# 03-Ethernet.net
KiCad netlist of a schematic drawn in Altium Designer
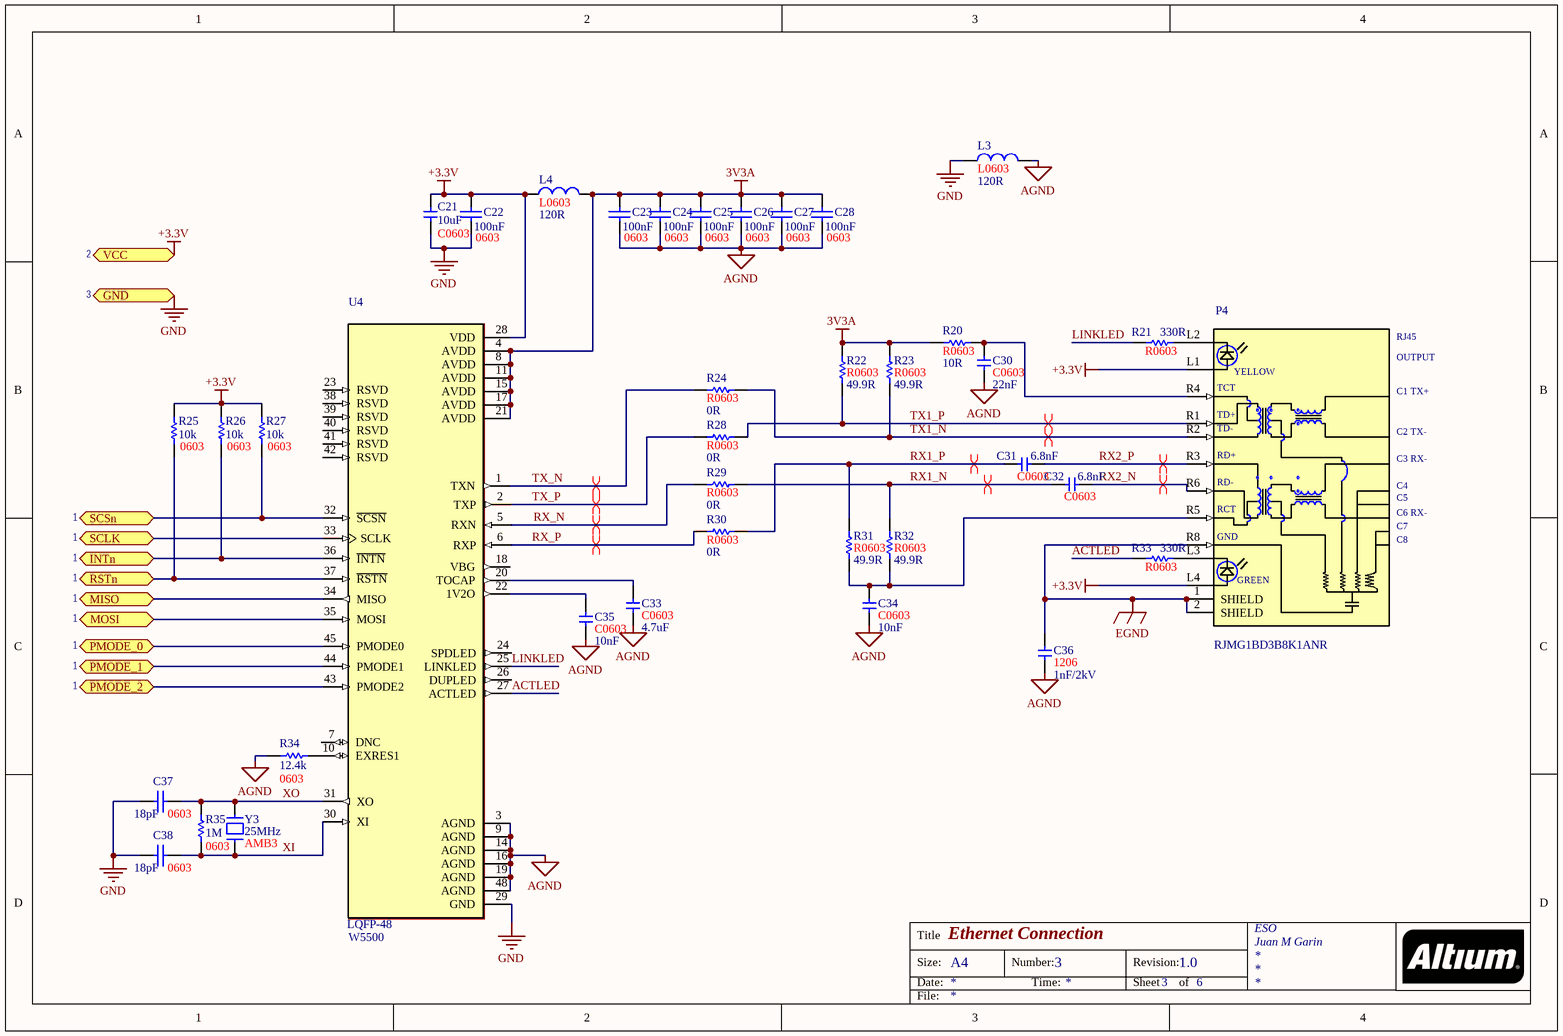
[diagram p0: 03-Ethernet.SchDoc]

(export (version "E")
  (design (tool "Eeschema 10.0.6"))
  (components
    (comp (ref "C21")
      (value "10uF")
      (footprint "C0603")
      (description "Capacitor")
      (fields
        (field (name "MANUFACTURER PART NUMBER") "JMK107ABJ106MA-T")
        (field (name "PACKAGEREFERENCE") "C0603")
      )
      (libsource (lib "schematic_library") (part "Cap_0603"))
    )
    (comp (ref "C22")
      (value "100nF")
      (footprint "C0603")
      (description "Capacitor (Semiconductor SIM Model)")
      (fields
        (field (name "MANUFACTURER PART NUMBER") "CL10F104ZO8NNNC")
        (field (name "PACKAGEREFERENCE") "0603")
      )
      (libsource (lib "Miscellaneous Devices") (part "Cap Semi"))
    )
    (comp (ref "C23")
      (value "100nF")
      (footprint "C0603")
      (description "Capacitor (Semiconductor SIM Model)")
      (fields
        (field (name "MANUFACTURER PART NUMBER") "CL10F104ZO8NNNC")
        (field (name "PACKAGEREFERENCE") "0603")
      )
      (libsource (lib "Miscellaneous Devices") (part "Cap Semi"))
    )
    (comp (ref "C24")
      (value "100nF")
      (footprint "C0603")
      (description "Capacitor (Semiconductor SIM Model)")
      (fields
        (field (name "MANUFACTURER PART NUMBER") "CL10F104ZO8NNNC")
        (field (name "PACKAGEREFERENCE") "0603")
      )
      (libsource (lib "Miscellaneous Devices") (part "Cap Semi"))
    )
    (comp (ref "C25")
      (value "100nF")
      (footprint "C0603")
      (description "Capacitor (Semiconductor SIM Model)")
      (fields
        (field (name "MANUFACTURER PART NUMBER") "CL10F104ZO8NNNC")
        (field (name "PACKAGEREFERENCE") "0603")
      )
      (libsource (lib "Miscellaneous Devices") (part "Cap Semi"))
    )
    (comp (ref "C26")
      (value "100nF")
      (footprint "C0603")
      (description "Capacitor (Semiconductor SIM Model)")
      (fields
        (field (name "MANUFACTURER PART NUMBER") "CL10F104ZO8NNNC")
        (field (name "PACKAGEREFERENCE") "0603")
      )
      (libsource (lib "Miscellaneous Devices") (part "Cap Semi"))
    )
    (comp (ref "C27")
      (value "100nF")
      (footprint "C0603")
      (description "Capacitor (Semiconductor SIM Model)")
      (fields
        (field (name "MANUFACTURER PART NUMBER") "CL10F104ZO8NNNC")
        (field (name "PACKAGEREFERENCE") "0603")
      )
      (libsource (lib "Miscellaneous Devices") (part "Cap Semi"))
    )
    (comp (ref "C28")
      (value "100nF")
      (footprint "C0603")
      (description "Capacitor (Semiconductor SIM Model)")
      (fields
        (field (name "MANUFACTURER PART NUMBER") "CL10F104ZO8NNNC")
        (field (name "PACKAGEREFERENCE") "0603")
      )
      (libsource (lib "Miscellaneous Devices") (part "Cap Semi"))
    )
    (comp (ref "C30")
      (value "22nF")
      (footprint "C0603")
      (description "Capacitor")
      (fields
        (field (name "MANUFACTURER PART NUMBER") "CL10B223KA8NNWC")
        (field (name "PACKAGEREFERENCE") "C0603")
      )
      (libsource (lib "schematic_library") (part "Cap_0402"))
    )
    (comp (ref "C31")
      (value "6.8nF")
      (footprint "C0603")
      (description "Capacitor")
      (fields
        (field (name "MANUFACTURER PART NUMBER") "CL10B682KB8SFNC")
        (field (name "PACKAGEREFERENCE") "C0603")
      )
      (libsource (lib "schematic_library") (part "Cap_0402"))
    )
    (comp (ref "C32")
      (value "6.8nF")
      (footprint "C0603")
      (description "Capacitor")
      (fields
        (field (name "MANUFACTURER PART NUMBER") "CL10B682KB8SFNC")
        (field (name "PACKAGEREFERENCE") "C0603")
      )
      (libsource (lib "schematic_library") (part "Cap_0402"))
    )
    (comp (ref "C33")
      (value "4.7uF")
      (footprint "C0603")
      (description "Capacitor")
      (fields
        (field (name "MANUFACTURER PART NUMBER") "CL10A475MP5LNNC")
        (field (name "PACKAGEREFERENCE") "C0603")
      )
      (libsource (lib "schematic_library") (part "Cap_0402"))
    )
    (comp (ref "C34")
      (value "10nF")
      (footprint "C0603")
      (description "Capacitor")
      (fields
        (field (name "MANUFACTURER PART NUMBER") "VJ0603Y103KXQCW1BC")
        (field (name "PACKAGEREFERENCE") "C0603")
      )
      (libsource (lib "schematic_library") (part "Cap_0402"))
    )
    (comp (ref "C35")
      (value "10nF")
      (footprint "C0603")
      (description "Capacitor")
      (fields
        (field (name "MANUFACTURER PART NUMBER") "VJ0603Y103KXQCW1BC")
        (field (name "PACKAGEREFERENCE") "C0603")
      )
      (libsource (lib "schematic_library") (part "Cap_0402"))
    )
    (comp (ref "C36")
      (value "1nF/2kV")
      (footprint "R1206")
      (description "Capacitor")
      (fields
        (field (name "MANUFACTURER PART NUMBER") "C1206C102KGRACAUTO")
        (field (name "PACKAGEREFERENCE") "1206")
      )
      (libsource (lib "Cycler_Assembly_v2") (part "Cap_1206"))
    )
    (comp (ref "C37")
      (value "18pF")
      (footprint "C0603")
      (description "Capacitor (Semiconductor SIM Model)")
      (fields
        (field (name "MANUFACTURER PART NUMBER") "VJ0603A180JXACW1BC")
        (field (name "PACKAGEREFERENCE") "0603")
      )
      (libsource (lib "Miscellaneous Devices") (part "Cap Semi"))
    )
    (comp (ref "C38")
      (value "18pF")
      (footprint "C0603")
      (description "Capacitor (Semiconductor SIM Model)")
      (fields
        (field (name "MANUFACTURER PART NUMBER") "VJ0603A180JXACW1BC")
        (field (name "PACKAGEREFERENCE") "0603")
      )
      (libsource (lib "Miscellaneous Devices") (part "Cap Semi"))
    )
    (comp (ref "L3")
      (value "120R")
      (footprint "L0603")
      (description "Inductor")
      (fields
        (field (name "MANUFACTURER PART NUMBER") "BLM18PG121SN1D")
        (field (name "PACKAGEREFERENCE") "L0603")
      )
      (libsource (lib "schematic_library") (part "Inductor_0603"))
    )
    (comp (ref "L4")
      (value "120R")
      (footprint "L0603")
      (description "Inductor")
      (fields
        (field (name "MANUFACTURER PART NUMBER") "BLM18PG121SN1D")
        (field (name "PACKAGEREFERENCE") "L0603")
      )
      (libsource (lib "schematic_library") (part "Inductor_0603"))
    )
    (comp (ref "P4")
      (value "RJMG1BD3B8K1ANR")
      (footprint "CONN_RJMG1BD3B8K1ANR_RJMG1BD3B8K1ANR(Primary)")
      (description "Accessory RJ-45 With Transformer Connector - UDE")
      (libsource (lib "Cycler_Assembly_v2") (part "RJMG1BD3B8K1ANR"))
    )
    (comp (ref "R20")
      (value "10R")
      (footprint "R0603")
      (description "Resistor")
      (fields
        (field (name "MANUFACTURER PART NUMBER") "RMCF0603JT10R0")
        (field (name "PACKAGEREFERENCE") "R0603")
      )
      (libsource (lib "schematic_library") (part "Res_0402"))
    )
    (comp (ref "R21")
      (value "330R")
      (footprint "R0603")
      (description "Resistor")
      (fields
        (field (name "MANUFACTURER PART NUMBER") "RMCF0603JT330R")
        (field (name "PACKAGEREFERENCE") "R0603")
      )
      (libsource (lib "schematic_library") (part "Res_0402"))
    )
    (comp (ref "R22")
      (value "49.9R")
      (footprint "R0603")
      (description "Resistor")
      (fields
        (field (name "MANUFACTURER PART NUMBER") "RMCF0603FT49R9")
        (field (name "PACKAGEREFERENCE") "R0603")
      )
      (libsource (lib "schematic_library") (part "Res_0402"))
    )
    (comp (ref "R23")
      (value "49.9R")
      (footprint "R0603")
      (description "Resistor")
      (fields
        (field (name "MANUFACTURER PART NUMBER") "RMCF0603FT49R9")
        (field (name "PACKAGEREFERENCE") "R0603")
      )
      (libsource (lib "schematic_library") (part "Res_0402"))
    )
    (comp (ref "R24")
      (value "0R")
      (footprint "R0603")
      (description "Resistor")
      (fields
        (field (name "MANUFACTURER PART NUMBER") "CR0603-J/-000ELF")
        (field (name "PACKAGEREFERENCE") "R0603")
      )
      (libsource (lib "schematic_library") (part "Res_0402"))
    )
    (comp (ref "R25")
      (value "10k")
      (footprint "R0603")
      (description "Resistor")
      (fields
        (field (name "MANUFACTURER PART NUMBER") "RMCF0603FT10K0")
        (field (name "PACKAGEREFERENCE") "0603")
      )
      (libsource (lib "Miscellaneous Devices") (part "Res1"))
    )
    (comp (ref "R26")
      (value "10k")
      (footprint "R0603")
      (description "Resistor")
      (fields
        (field (name "MANUFACTURER PART NUMBER") "RMCF0603FT10K0")
        (field (name "PACKAGEREFERENCE") "0603")
      )
      (libsource (lib "Miscellaneous Devices") (part "Res1"))
    )
    (comp (ref "R27")
      (value "10k")
      (footprint "R0603")
      (description "Resistor")
      (fields
        (field (name "MANUFACTURER PART NUMBER") "RMCF0603FT10K0")
        (field (name "PACKAGEREFERENCE") "0603")
      )
      (libsource (lib "Miscellaneous Devices") (part "Res1"))
    )
    (comp (ref "R28")
      (value "0R")
      (footprint "R0603")
      (description "Resistor")
      (fields
        (field (name "MANUFACTURER PART NUMBER") "CR0603-J/-000ELF")
        (field (name "PACKAGEREFERENCE") "R0603")
      )
      (libsource (lib "schematic_library") (part "Res_0402"))
    )
    (comp (ref "R29")
      (value "0R")
      (footprint "R0603")
      (description "Resistor")
      (fields
        (field (name "MANUFACTURER PART NUMBER") "CR0603-J/-000ELF")
        (field (name "PACKAGEREFERENCE") "R0603")
      )
      (libsource (lib "schematic_library") (part "Res_0402"))
    )
    (comp (ref "R30")
      (value "0R")
      (footprint "R0603")
      (description "Resistor")
      (fields
        (field (name "MANUFACTURER PART NUMBER") "CR0603-J/-000ELF")
        (field (name "PACKAGEREFERENCE") "R0603")
      )
      (libsource (lib "schematic_library") (part "Res_0402"))
    )
    (comp (ref "R31")
      (value "49.9R")
      (footprint "R0603")
      (description "Resistor")
      (fields
        (field (name "MANUFACTURER PART NUMBER") "RMCF0603FT49R9")
        (field (name "PACKAGEREFERENCE") "R0603")
      )
      (libsource (lib "schematic_library") (part "Res_0402"))
    )
    (comp (ref "R32")
      (value "49.9R")
      (footprint "R0603")
      (description "Resistor")
      (fields
        (field (name "MANUFACTURER PART NUMBER") "RMCF0603FT49R9")
        (field (name "PACKAGEREFERENCE") "R0603")
      )
      (libsource (lib "schematic_library") (part "Res_0402"))
    )
    (comp (ref "R33")
      (value "330R")
      (footprint "R0603")
      (description "Resistor")
      (fields
        (field (name "MANUFACTURER PART NUMBER") "RMCF0603JT330R")
        (field (name "PACKAGEREFERENCE") "R0603")
      )
      (libsource (lib "schematic_library") (part "Res_0402"))
    )
    (comp (ref "R34")
      (value "12.4k")
      (footprint "R0603")
      (description "Resistor")
      (fields
        (field (name "MANUFACTURER PART NUMBER") "RMCF0603FT12K4")
        (field (name "PACKAGEREFERENCE") "0603")
      )
      (libsource (lib "Miscellaneous Devices") (part "Res1"))
    )
    (comp (ref "R35")
      (value "1M")
      (footprint "R0603")
      (description "Resistor")
      (fields
        (field (name "MANUFACTURER PART NUMBER") "RMCF0603FG1M00")
        (field (name "PACKAGEREFERENCE") "0603")
      )
      (libsource (lib "Miscellaneous Devices") (part "Res1"))
    )
    (comp (ref "U4")
      (value "W5500")
      (footprint "QFP50P700X700X160-48N")
      (description "Victor Pure White Collection Wood Tidy Tower Organizer")
      (fields (field (name "PACKAGEREFERENCE") "LQFP-48"))
      (libsource (lib "Cycler_Assembly_v2") (part "W5500"))
    )
    (comp (ref "Y3")
      (value "25MHz")
      (footprint "CRYSTAL-AMB3_5X3.2_1.3")
      (description "Crystal")
      (fields
        (field (name "MANUFACTURER PART NUMBER") "ABM3-25.000MHZ-D2Y-T")
        (field (name "PACKAGEREFERENCE") "AMB3")
      )
      (libsource (lib "schematic_library") (part "CRYSTAL"))
    )
  )
  (nets
    (net (code "1") (name "+3.3V") (class "Default")
      (node (ref "C21") (pin "2") (pinfunction "2_2") (pintype "passive"))
      (node (ref "C22") (pin "2") (pinfunction "2_2") (pintype "passive"))
      (node (ref "L4") (pin "1") (pinfunction "1_1") (pintype "passive"))
      (node (ref "P4") (pin "L1") (pinfunction "L1_L1") (pintype "passive"))
      (node (ref "P4") (pin "L4") (pinfunction "L4_L4") (pintype "passive"))
      (node (ref "R25") (pin "1") (pinfunction "1_1") (pintype "passive"))
      (node (ref "R26") (pin "1") (pinfunction "1_1") (pintype "passive"))
      (node (ref "R27") (pin "1") (pinfunction "1_1") (pintype "passive"))
      (node (ref "U4") (pin "28") (pinfunction "VDD_28") (pintype "power_in"))
    )
    (net (code "2") (name "/ACTLED") (class "Default")
      (node (ref "R33") (pin "1") (pinfunction "1_1") (pintype "passive"))
      (node (ref "U4") (pin "27") (pinfunction "ACTLED_27") (pintype "output"))
    )
    (net (code "3") (name "/INTn") (class "Default")
      (node (ref "R26") (pin "2") (pinfunction "2_2") (pintype "passive"))
      (node (ref "U4") (pin "36") (pinfunction "~{INTN}_36") (pintype "input"))
    )
    (net (code "4") (name "/LINKLED") (class "Default")
      (node (ref "R21") (pin "1") (pinfunction "1_1") (pintype "passive"))
      (node (ref "U4") (pin "25") (pinfunction "LINKLED_25") (pintype "output"))
    )
    (net (code "5") (name "/MISO") (class "Default")
      (node (ref "U4") (pin "34") (pinfunction "MISO_34") (pintype "output"))
    )
    (net (code "6") (name "/MOSI") (class "Default")
      (node (ref "U4") (pin "35") (pinfunction "MOSI_35") (pintype "input"))
    )
    (net (code "7") (name "/PMODE_0") (class "Default")
      (node (ref "U4") (pin "45") (pinfunction "PMODE0_45") (pintype "input"))
    )
    (net (code "8") (name "/PMODE_1") (class "Default")
      (node (ref "U4") (pin "44") (pinfunction "PMODE1_44") (pintype "input"))
    )
    (net (code "9") (name "/PMODE_2") (class "Default")
      (node (ref "U4") (pin "43") (pinfunction "PMODE2_43") (pintype "input"))
    )
    (net (code "10") (name "/RSTn") (class "Default")
      (node (ref "R25") (pin "2") (pinfunction "2_2") (pintype "passive"))
      (node (ref "U4") (pin "37") (pinfunction "~{RSTN}_37") (pintype "input"))
    )
    (net (code "11") (name "/RX1_N") (class "Default")
      (node (ref "C32") (pin "2") (pinfunction "2_2") (pintype "passive"))
      (node (ref "R29") (pin "2") (pinfunction "2_2") (pintype "passive"))
      (node (ref "R32") (pin "1") (pinfunction "1_1") (pintype "passive"))
    )
    (net (code "12") (name "/RX1_P") (class "Default")
      (node (ref "C31") (pin "2") (pinfunction "2_2") (pintype "passive"))
      (node (ref "R30") (pin "2") (pinfunction "2_2") (pintype "passive"))
      (node (ref "R31") (pin "1") (pinfunction "1_1") (pintype "passive"))
    )
    (net (code "13") (name "/RX2_N") (class "Default")
      (node (ref "C32") (pin "1") (pinfunction "1_1") (pintype "passive"))
      (node (ref "P4") (pin "R6") (pinfunction "RD-_R6") (pintype "input"))
    )
    (net (code "14") (name "/RX2_P") (class "Default")
      (node (ref "C31") (pin "1") (pinfunction "1_1") (pintype "passive"))
      (node (ref "P4") (pin "R3") (pinfunction "RD+_R3") (pintype "input"))
    )
    (net (code "15") (name "/RX_N") (class "Default")
      (node (ref "R29") (pin "1") (pinfunction "1_1") (pintype "passive"))
      (node (ref "U4") (pin "5") (pinfunction "RXN_5") (pintype "input"))
    )
    (net (code "16") (name "/RX_P") (class "Default")
      (node (ref "R30") (pin "1") (pinfunction "1_1") (pintype "passive"))
      (node (ref "U4") (pin "6") (pinfunction "RXP_6") (pintype "input"))
    )
    (net (code "17") (name "/SCLK") (class "Default")
      (node (ref "U4") (pin "33") (pinfunction "SCLK_33") (pintype "input"))
    )
    (net (code "18") (name "/SCSn") (class "Default")
      (node (ref "R27") (pin "2") (pinfunction "2_2") (pintype "passive"))
      (node (ref "U4") (pin "32") (pinfunction "~{SCSN}_32") (pintype "input"))
    )
    (net (code "19") (name "/TX1_N") (class "Default")
      (node (ref "P4") (pin "R2") (pinfunction "TD-_R2") (pintype "input"))
      (node (ref "R23") (pin "2") (pinfunction "2_2") (pintype "passive"))
      (node (ref "R24") (pin "2") (pinfunction "2_2") (pintype "passive"))
    )
    (net (code "20") (name "/TX1_P") (class "Default")
      (node (ref "P4") (pin "R1") (pinfunction "TD+_R1") (pintype "input"))
      (node (ref "R22") (pin "2") (pinfunction "2_2") (pintype "passive"))
      (node (ref "R28") (pin "2") (pinfunction "2_2") (pintype "passive"))
    )
    (net (code "21") (name "/TX_N") (class "Default")
      (node (ref "R24") (pin "1") (pinfunction "1_1") (pintype "passive"))
      (node (ref "U4") (pin "1") (pinfunction "TXN_1") (pintype "output"))
    )
    (net (code "22") (name "/TX_P") (class "Default")
      (node (ref "R28") (pin "1") (pinfunction "1_1") (pintype "passive"))
      (node (ref "U4") (pin "2") (pinfunction "TXP_2") (pintype "output"))
    )
    (net (code "23") (name "/XI") (class "Default")
      (node (ref "C38") (pin "1") (pinfunction "1_1") (pintype "passive"))
      (node (ref "R35") (pin "1") (pinfunction "1_1") (pintype "passive"))
      (node (ref "U4") (pin "30") (pinfunction "XI_30") (pintype "input"))
      (node (ref "Y3") (pin "1") (pinfunction "1_1") (pintype "passive"))
    )
    (net (code "24") (name "/XO") (class "Default")
      (node (ref "C37") (pin "1") (pinfunction "1_1") (pintype "passive"))
      (node (ref "R35") (pin "2") (pinfunction "2_2") (pintype "passive"))
      (node (ref "U4") (pin "31") (pinfunction "XO_31") (pintype "output"))
      (node (ref "Y3") (pin "2") (pinfunction "2_2") (pintype "passive"))
    )
    (net (code "25") (name "3V3A") (class "Default")
      (node (ref "C23") (pin "2") (pinfunction "2_2") (pintype "passive"))
      (node (ref "C24") (pin "2") (pinfunction "2_2") (pintype "passive"))
      (node (ref "C25") (pin "2") (pinfunction "2_2") (pintype "passive"))
      (node (ref "C26") (pin "2") (pinfunction "2_2") (pintype "passive"))
      (node (ref "C27") (pin "2") (pinfunction "2_2") (pintype "passive"))
      (node (ref "C28") (pin "2") (pinfunction "2_2") (pintype "passive"))
      (node (ref "L4") (pin "2") (pinfunction "2_2") (pintype "passive"))
      (node (ref "R20") (pin "1") (pinfunction "1_1") (pintype "passive"))
      (node (ref "R22") (pin "1") (pinfunction "1_1") (pintype "passive"))
      (node (ref "R23") (pin "1") (pinfunction "1_1") (pintype "passive"))
      (node (ref "U4") (pin "11") (pinfunction "AVDD_11") (pintype "power_in"))
      (node (ref "U4") (pin "15") (pinfunction "AVDD_15") (pintype "power_in"))
      (node (ref "U4") (pin "17") (pinfunction "AVDD_17") (pintype "power_in"))
      (node (ref "U4") (pin "21") (pinfunction "AVDD_21") (pintype "power_in"))
      (node (ref "U4") (pin "4") (pinfunction "AVDD_4") (pintype "power_in"))
      (node (ref "U4") (pin "8") (pinfunction "AVDD_8") (pintype "power_in"))
    )
    (net (code "26") (name "AGND") (class "Default")
      (node (ref "C23") (pin "1") (pinfunction "1_1") (pintype "passive"))
      (node (ref "C24") (pin "1") (pinfunction "1_1") (pintype "passive"))
      (node (ref "C25") (pin "1") (pinfunction "1_1") (pintype "passive"))
      (node (ref "C26") (pin "1") (pinfunction "1_1") (pintype "passive"))
      (node (ref "C27") (pin "1") (pinfunction "1_1") (pintype "passive"))
      (node (ref "C28") (pin "1") (pinfunction "1_1") (pintype "passive"))
      (node (ref "C30") (pin "1") (pinfunction "1_1") (pintype "passive"))
      (node (ref "C33") (pin "1") (pinfunction "1_1") (pintype "passive"))
      (node (ref "C34") (pin "1") (pinfunction "1_1") (pintype "passive"))
      (node (ref "C35") (pin "1") (pinfunction "1_1") (pintype "passive"))
      (node (ref "C36") (pin "1") (pinfunction "1_1") (pintype "passive"))
      (node (ref "L3") (pin "2") (pinfunction "2_2") (pintype "passive"))
      (node (ref "R34") (pin "1") (pinfunction "1_1") (pintype "passive"))
      (node (ref "U4") (pin "14") (pinfunction "AGND_14") (pintype "passive"))
      (node (ref "U4") (pin "16") (pinfunction "AGND_16") (pintype "passive"))
      (node (ref "U4") (pin "19") (pinfunction "AGND_19") (pintype "passive"))
      (node (ref "U4") (pin "3") (pinfunction "AGND_3") (pintype "passive"))
      (node (ref "U4") (pin "48") (pinfunction "AGND_48") (pintype "passive"))
      (node (ref "U4") (pin "9") (pinfunction "AGND_9") (pintype "passive"))
    )
    (net (code "27") (name "EGND") (class "Default")
      (node (ref "C36") (pin "2") (pinfunction "2_2") (pintype "passive"))
      (node (ref "P4") (pin "1") (pinfunction "SHIELD_1") (pintype "passive"))
      (node (ref "P4") (pin "2") (pinfunction "SHIELD_2") (pintype "passive"))
      (node (ref "P4") (pin "R8") (pinfunction "GND_R8") (pintype "input"))
    )
    (net (code "28") (name "GND") (class "Default")
      (node (ref "C21") (pin "1") (pinfunction "1_1") (pintype "passive"))
      (node (ref "C22") (pin "1") (pinfunction "1_1") (pintype "passive"))
      (node (ref "C37") (pin "2") (pinfunction "2_2") (pintype "passive"))
      (node (ref "C38") (pin "2") (pinfunction "2_2") (pintype "passive"))
      (node (ref "L3") (pin "1") (pinfunction "1_1") (pintype "passive"))
      (node (ref "U4") (pin "29") (pinfunction "GND_29") (pintype "passive"))
    )
    (net (code "29") (name "Net-(P4-PadL2)") (class "Default")
      (node (ref "P4") (pin "L2") (pinfunction "L2_L2") (pintype "passive"))
      (node (ref "R21") (pin "2") (pinfunction "2_2") (pintype "passive"))
    )
    (net (code "30") (name "Net-(P4-PadL3)") (class "Default")
      (node (ref "P4") (pin "L3") (pinfunction "L3_L3") (pintype "passive"))
      (node (ref "R33") (pin "2") (pinfunction "2_2") (pintype "passive"))
    )
    (net (code "31") (name "Net-(P4-RCT)") (class "Default")
      (node (ref "C34") (pin "2") (pinfunction "2_2") (pintype "passive"))
      (node (ref "P4") (pin "R5") (pinfunction "RCT_R5") (pintype "input"))
      (node (ref "R31") (pin "2") (pinfunction "2_2") (pintype "passive"))
      (node (ref "R32") (pin "2") (pinfunction "2_2") (pintype "passive"))
    )
    (net (code "32") (name "Net-(P4-TCT)") (class "Default")
      (node (ref "C30") (pin "2") (pinfunction "2_2") (pintype "passive"))
      (node (ref "P4") (pin "R4") (pinfunction "TCT_R4") (pintype "input"))
      (node (ref "R20") (pin "2") (pinfunction "2_2") (pintype "passive"))
    )
    (net (code "33") (name "Net-(U4-1V2O)") (class "Default")
      (node (ref "C35") (pin "2") (pinfunction "2_2") (pintype "passive"))
      (node (ref "U4") (pin "22") (pinfunction "1V2O_22") (pintype "output"))
    )
    (net (code "34") (name "Net-(U4-EXRES1)") (class "Default")
      (node (ref "R34") (pin "2") (pinfunction "2_2") (pintype "passive"))
      (node (ref "U4") (pin "10") (pinfunction "EXRES1_10") (pintype "bidirectional"))
    )
    (net (code "35") (name "Net-(U4-TOCAP)") (class "Default")
      (node (ref "C33") (pin "2") (pinfunction "2_2") (pintype "passive"))
      (node (ref "U4") (pin "20") (pinfunction "TOCAP_20") (pintype "output"))
    )
    (net (code "36") (name "unconnected-(U4-DNC-Pad7)") (class "Default")
      (node (ref "U4") (pin "7") (pinfunction "DNC_7") (pintype "bidirectional"))
    )
    (net (code "37") (name "unconnected-(U4-DUPLED-Pad26)") (class "Default")
      (node (ref "U4") (pin "26") (pinfunction "DUPLED_26") (pintype "output"))
    )
    (net (code "38") (name "unconnected-(U4-RSVD-Pad23)") (class "Default")
      (node (ref "U4") (pin "23") (pinfunction "RSVD_23") (pintype "input"))
    )
    (net (code "39") (name "unconnected-(U4-RSVD-Pad38)") (class "Default")
      (node (ref "U4") (pin "38") (pinfunction "RSVD_38") (pintype "input"))
    )
    (net (code "40") (name "unconnected-(U4-RSVD-Pad39)") (class "Default")
      (node (ref "U4") (pin "39") (pinfunction "RSVD_39") (pintype "input"))
    )
    (net (code "41") (name "unconnected-(U4-RSVD-Pad40)") (class "Default")
      (node (ref "U4") (pin "40") (pinfunction "RSVD_40") (pintype "input"))
    )
    (net (code "42") (name "unconnected-(U4-RSVD-Pad41)") (class "Default")
      (node (ref "U4") (pin "41") (pinfunction "RSVD_41") (pintype "input"))
    )
    (net (code "43") (name "unconnected-(U4-RSVD-Pad42)") (class "Default")
      (node (ref "U4") (pin "42") (pinfunction "RSVD_42") (pintype "input"))
    )
    (net (code "44") (name "unconnected-(U4-SPDLED-Pad24)") (class "Default")
      (node (ref "U4") (pin "24") (pinfunction "SPDLED_24") (pintype "output"))
    )
    (net (code "45") (name "unconnected-(U4-VBG-Pad18)") (class "Default")
      (node (ref "U4") (pin "18") (pinfunction "VBG_18") (pintype "output"))
    )
  )
)
